# RAMPSXB.net
KiCad netlist of a schematic drawn in EAGLE
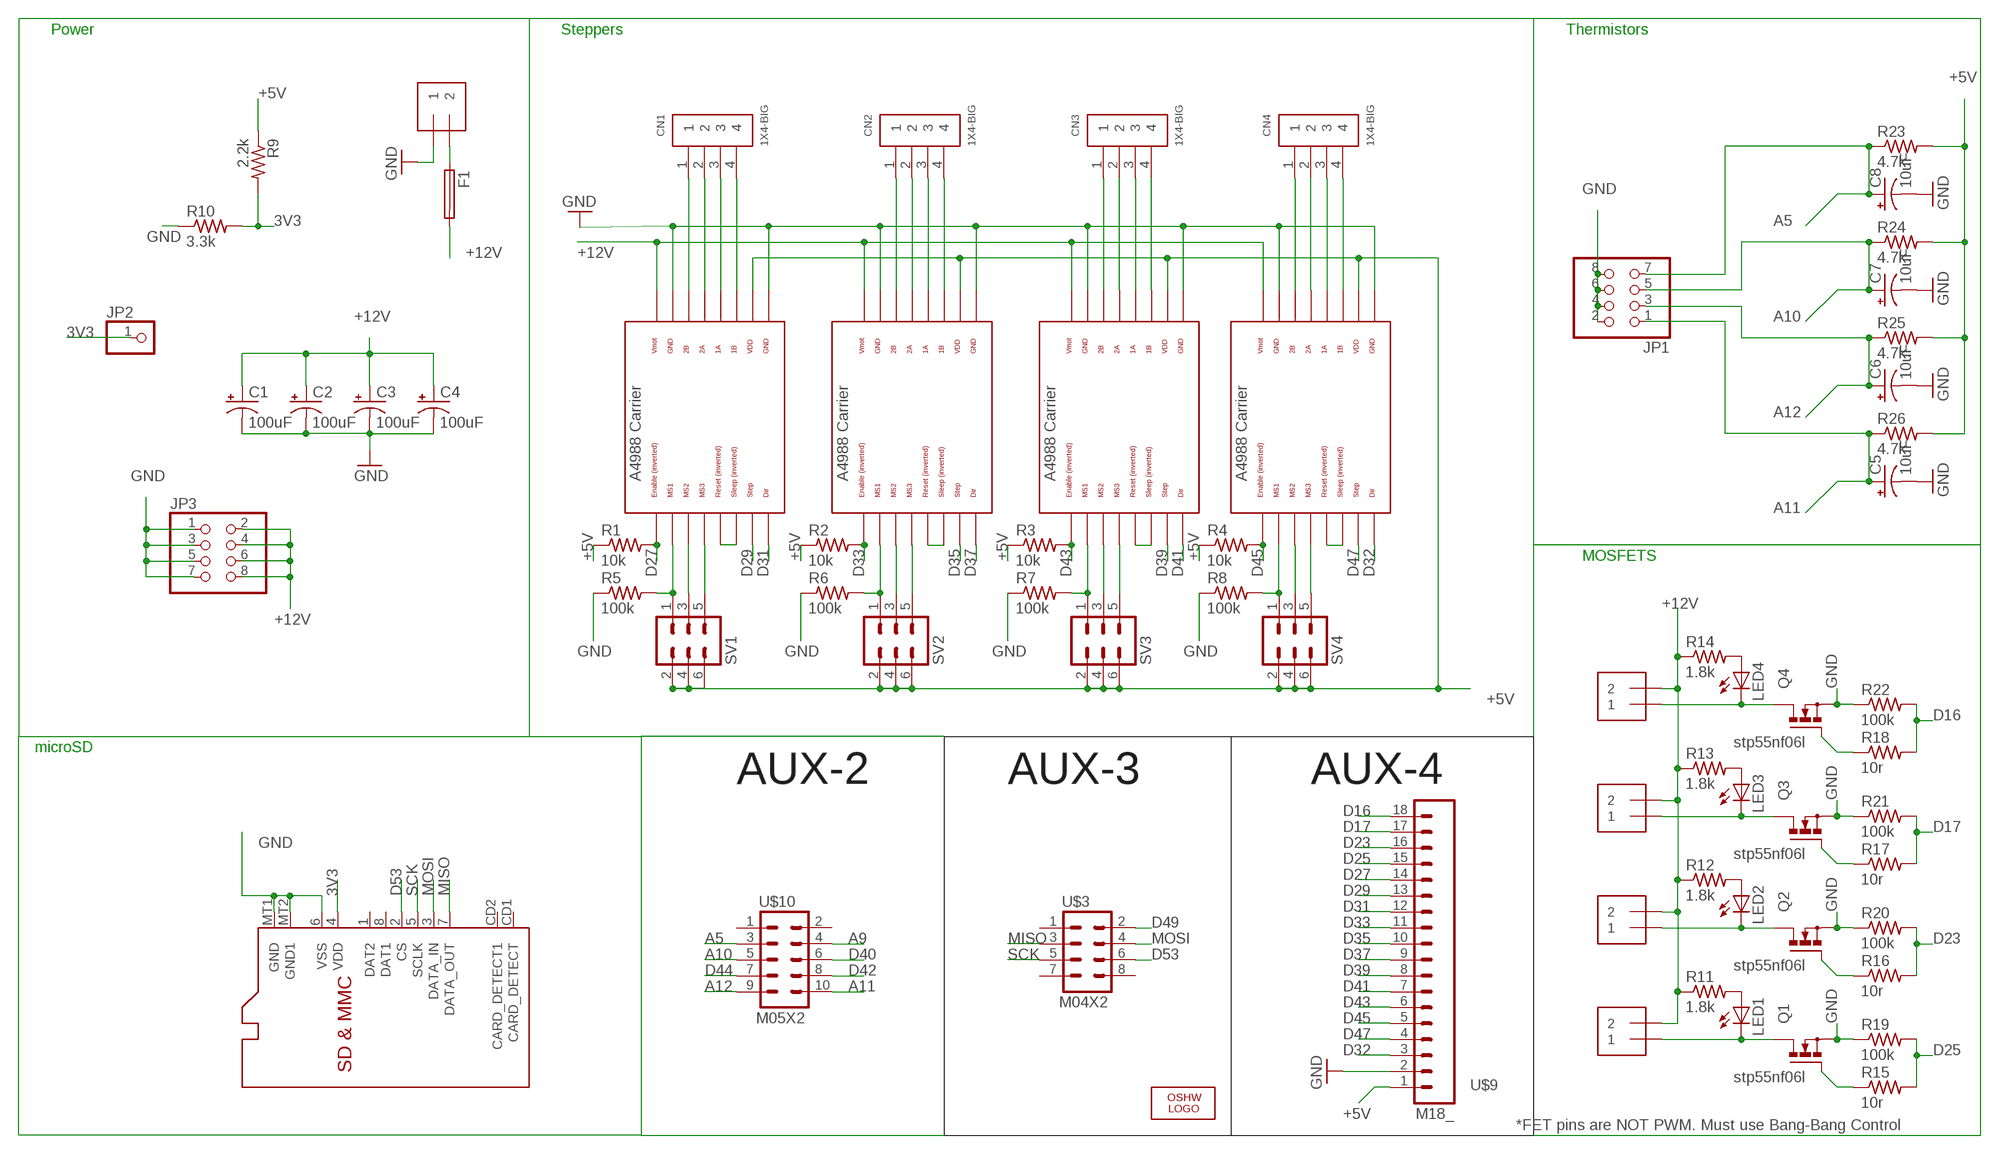
[diagram p0: schematic, sheet 1]

(export (version "E")
  (design (tool "Eeschema 10.0.6"))
  (components
    (comp (ref "C1")
      (value "100uF")
      (footprint "eagle-import:153CLV-0605")
      (libsource (lib "eagle-import") (part "CPOL-US153CLV-0605"))
    )
    (comp (ref "C2")
      (value "100uF")
      (footprint "eagle-import:153CLV-0605")
      (libsource (lib "eagle-import") (part "CPOL-US153CLV-0605"))
    )
    (comp (ref "C3")
      (value "100uF")
      (footprint "eagle-import:153CLV-0605")
      (libsource (lib "eagle-import") (part "CPOL-US153CLV-0605"))
    )
    (comp (ref "C4")
      (value "100uF")
      (footprint "eagle-import:153CLV-0605")
      (libsource (lib "eagle-import") (part "CPOL-US153CLV-0605"))
    )
    (comp (ref "C5")
      (value "10uF")
      (footprint "eagle-import:153CLV-0405")
      (libsource (lib "eagle-import") (part "CPOL-US153CLV-0405"))
    )
    (comp (ref "C6")
      (value "10uF")
      (footprint "eagle-import:153CLV-0405")
      (libsource (lib "eagle-import") (part "CPOL-US153CLV-0405"))
    )
    (comp (ref "C7")
      (value "10uF")
      (footprint "eagle-import:153CLV-0405")
      (libsource (lib "eagle-import") (part "CPOL-US153CLV-0405"))
    )
    (comp (ref "C8")
      (value "10uF")
      (footprint "eagle-import:153CLV-0405")
      (libsource (lib "eagle-import") (part "CPOL-US153CLV-0405"))
    )
    (comp (ref "CN1")
      (value "1X4-BIG")
      (footprint "eagle-import:1X04-BIG")
      (libsource (lib "eagle-import") (part "1X4-BIG"))
    )
    (comp (ref "CN2")
      (value "1X4-BIG")
      (footprint "eagle-import:1X04-BIG")
      (libsource (lib "eagle-import") (part "1X4-BIG"))
    )
    (comp (ref "CN3")
      (value "1X4-BIG")
      (footprint "eagle-import:1X04-BIG")
      (libsource (lib "eagle-import") (part "1X4-BIG"))
    )
    (comp (ref "CN4")
      (value "1X4-BIG")
      (footprint "eagle-import:1X04-BIG")
      (libsource (lib "eagle-import") (part "1X4-BIG"))
    )
    (comp (ref "F1")
      (value "SH22,5")
      (footprint "eagle-import:SH22,5")
      (fields (field (name "MF") "SCHURTER") (field (name "MPN") "0031.8201"))
      (libsource (lib "eagle-import") (part "SH22,5"))
    )
    (comp (ref "J1")
      (value "1X2-3.5MM")
      (footprint "eagle-import:1X2-3.5MM")
      (libsource (lib "eagle-import") (part "1X2-3.5MM"))
    )
    (comp (ref "J2")
      (value "1X2-3.5MM")
      (footprint "eagle-import:1X2-3.5MM")
      (libsource (lib "eagle-import") (part "1X2-3.5MM"))
    )
    (comp (ref "J3")
      (value "1X2-3.5MM")
      (footprint "eagle-import:1X2-3.5MM")
      (libsource (lib "eagle-import") (part "1X2-3.5MM"))
    )
    (comp (ref "J4")
      (value "1X2-3.5MM")
      (footprint "eagle-import:1X2-3.5MM")
      (libsource (lib "eagle-import") (part "1X2-3.5MM"))
    )
    (comp (ref "J5")
      (value "1X2-3.5MM")
      (footprint "eagle-import:1X2-3.5MM")
      (libsource (lib "eagle-import") (part "1X2-3.5MM"))
    )
    (comp (ref "JP1")
      (value "PINHD-2X4")
      (footprint "eagle-import:2X04")
      (libsource (lib "eagle-import") (part "PINHD-2X4"))
    )
    (comp (ref "JP2")
      (value "PINHD-1X1")
      (footprint "eagle-import:1X01")
      (libsource (lib "eagle-import") (part "PINHD-1X1"))
    )
    (comp (ref "JP3")
      (value "PINHD-2X4")
      (footprint "eagle-import:2X04")
      (libsource (lib "eagle-import") (part "PINHD-2X4"))
    )
    (comp (ref "LED1")
      (value "LEDCHIPLED_0805")
      (footprint "eagle-import:CHIPLED_0805")
      (libsource (lib "eagle-import") (part "LEDCHIPLED_0805"))
    )
    (comp (ref "LED2")
      (value "LEDCHIPLED_0805")
      (footprint "eagle-import:CHIPLED_0805")
      (libsource (lib "eagle-import") (part "LEDCHIPLED_0805"))
    )
    (comp (ref "LED3")
      (value "LEDCHIPLED_0805")
      (footprint "eagle-import:CHIPLED_0805")
      (libsource (lib "eagle-import") (part "LEDCHIPLED_0805"))
    )
    (comp (ref "LED4")
      (value "LEDCHIPLED_0805")
      (footprint "eagle-import:CHIPLED_0805")
      (libsource (lib "eagle-import") (part "LEDCHIPLED_0805"))
    )
    (comp (ref "LOGO1")
      (value "OSHW_LOGO_6MILX0100-NT")
      (footprint "eagle-import:OSHW_6X100_NOTEXT")
      (libsource (lib "eagle-import") (part "OSHW_LOGO_6MILX0100-NT"))
    )
    (comp (ref "Q1")
      (value "IRF512")
      (footprint "eagle-import:TO220BV")
      (libsource (lib "eagle-import") (part "IRF512"))
    )
    (comp (ref "Q2")
      (value "IRF512")
      (footprint "eagle-import:TO220BV")
      (libsource (lib "eagle-import") (part "IRF512"))
    )
    (comp (ref "Q3")
      (value "IRF512")
      (footprint "eagle-import:TO220BV")
      (libsource (lib "eagle-import") (part "IRF512"))
    )
    (comp (ref "Q4")
      (value "IRF512")
      (footprint "eagle-import:TO220BV")
      (libsource (lib "eagle-import") (part "IRF512"))
    )
    (comp (ref "R1")
      (value "10k")
      (footprint "eagle-import:M0805")
      (libsource (lib "eagle-import") (part "R-US_M0805"))
    )
    (comp (ref "R2")
      (value "10k")
      (footprint "eagle-import:M0805")
      (libsource (lib "eagle-import") (part "R-US_M0805"))
    )
    (comp (ref "R3")
      (value "10k")
      (footprint "eagle-import:M0805")
      (libsource (lib "eagle-import") (part "R-US_M0805"))
    )
    (comp (ref "R4")
      (value "10k")
      (footprint "eagle-import:M0805")
      (libsource (lib "eagle-import") (part "R-US_M0805"))
    )
    (comp (ref "R5")
      (value "100k")
      (footprint "eagle-import:M0805")
      (libsource (lib "eagle-import") (part "R-US_M0805"))
    )
    (comp (ref "R6")
      (value "100k")
      (footprint "eagle-import:M0805")
      (libsource (lib "eagle-import") (part "R-US_M0805"))
    )
    (comp (ref "R7")
      (value "100k")
      (footprint "eagle-import:M0805")
      (libsource (lib "eagle-import") (part "R-US_M0805"))
    )
    (comp (ref "R8")
      (value "100k")
      (footprint "eagle-import:M0805")
      (libsource (lib "eagle-import") (part "R-US_M0805"))
    )
    (comp (ref "R9")
      (value "2.2k")
      (footprint "eagle-import:M1206")
      (libsource (lib "eagle-import") (part "R-US_M1206"))
    )
    (comp (ref "R10")
      (value "3.3k")
      (footprint "eagle-import:M1206")
      (libsource (lib "eagle-import") (part "R-US_M1206"))
    )
    (comp (ref "R11")
      (value "1.8k")
      (footprint "eagle-import:M0805")
      (libsource (lib "eagle-import") (part "R-US_M0805"))
    )
    (comp (ref "R12")
      (value "1.8k")
      (footprint "eagle-import:M0805")
      (libsource (lib "eagle-import") (part "R-US_M0805"))
    )
    (comp (ref "R13")
      (value "1.8k")
      (footprint "eagle-import:M0805")
      (libsource (lib "eagle-import") (part "R-US_M0805"))
    )
    (comp (ref "R14")
      (value "1.8k")
      (footprint "eagle-import:M0805")
      (libsource (lib "eagle-import") (part "R-US_M0805"))
    )
    (comp (ref "R15")
      (value "10r")
      (footprint "eagle-import:M0805")
      (libsource (lib "eagle-import") (part "R-US_M0805"))
    )
    (comp (ref "R16")
      (value "10r")
      (footprint "eagle-import:M0805")
      (libsource (lib "eagle-import") (part "R-US_M0805"))
    )
    (comp (ref "R17")
      (value "10r")
      (footprint "eagle-import:M0805")
      (libsource (lib "eagle-import") (part "R-US_M0805"))
    )
    (comp (ref "R18")
      (value "10r")
      (footprint "eagle-import:M0805")
      (libsource (lib "eagle-import") (part "R-US_M0805"))
    )
    (comp (ref "R19")
      (value "100k")
      (footprint "eagle-import:M0805")
      (libsource (lib "eagle-import") (part "R-US_M0805"))
    )
    (comp (ref "R20")
      (value "100k")
      (footprint "eagle-import:M0805")
      (libsource (lib "eagle-import") (part "R-US_M0805"))
    )
    (comp (ref "R21")
      (value "100k")
      (footprint "eagle-import:M0805")
      (libsource (lib "eagle-import") (part "R-US_M0805"))
    )
    (comp (ref "R22")
      (value "100k")
      (footprint "eagle-import:M0805")
      (libsource (lib "eagle-import") (part "R-US_M0805"))
    )
    (comp (ref "R23")
      (value "4.7k")
      (footprint "eagle-import:R0805")
      (libsource (lib "eagle-import") (part "R-US_R0805"))
    )
    (comp (ref "R24")
      (value "4.7k")
      (footprint "eagle-import:R0805")
      (libsource (lib "eagle-import") (part "R-US_R0805"))
    )
    (comp (ref "R25")
      (value "4.7k")
      (footprint "eagle-import:R0805")
      (libsource (lib "eagle-import") (part "R-US_R0805"))
    )
    (comp (ref "R26")
      (value "4.7k")
      (footprint "eagle-import:R0805")
      (libsource (lib "eagle-import") (part "R-US_R0805"))
    )
    (comp (ref "SV1")
      (value "MA03-2")
      (footprint "eagle-import:MA03-2")
      (libsource (lib "eagle-import") (part "MA03-2"))
    )
    (comp (ref "SV2")
      (value "MA03-2")
      (footprint "eagle-import:MA03-2")
      (libsource (lib "eagle-import") (part "MA03-2"))
    )
    (comp (ref "SV3")
      (value "MA03-2")
      (footprint "eagle-import:MA03-2")
      (libsource (lib "eagle-import") (part "MA03-2"))
    )
    (comp (ref "SV4")
      (value "MA03-2")
      (footprint "eagle-import:MA03-2")
      (libsource (lib "eagle-import") (part "MA03-2"))
    )
    (comp (ref "U$1")
      (value "POLOLU_A4983CARRIER")
      (footprint "eagle-import:A4988BREAKOUT")
      (libsource (lib "eagle-import") (part "POLOLU_A4983CARRIER"))
    )
    (comp (ref "U$2")
      (value "POLOLU_A4983CARRIER")
      (footprint "eagle-import:A4988BREAKOUT")
      (libsource (lib "eagle-import") (part "POLOLU_A4983CARRIER"))
    )
    (comp (ref "U$3")
      (value "M04X2")
      (footprint "eagle-import:2X4")
      (libsource (lib "eagle-import") (part "M04X2"))
    )
    (comp (ref "U$4")
      (value "POLOLU_A4983CARRIER")
      (footprint "eagle-import:A4988BREAKOUT")
      (libsource (lib "eagle-import") (part "POLOLU_A4983CARRIER"))
    )
    (comp (ref "U$5")
      (value "POLOLU_A4983CARRIER")
      (footprint "eagle-import:A4988BREAKOUT")
      (libsource (lib "eagle-import") (part "POLOLU_A4983CARRIER"))
    )
    (comp (ref "U$6")
      (value "MICROSD")
      (footprint "eagle-import:MICROSD")
      (libsource (lib "eagle-import") (part "MICROSD"))
    )
    (comp (ref "U$9")
      (value "M18_")
      (footprint "eagle-import:1X18")
      (libsource (lib "eagle-import") (part "M18_"))
    )
    (comp (ref "U$10")
      (value "M05X2")
      (footprint "eagle-import:2X5")
      (libsource (lib "eagle-import") (part "M05X2"))
    )
  )
  (nets
    (net (code "1") (name "/+5V") (class "Default")
      (node (ref "R1") (pin "1") (pinfunction "1_1") (pintype "passive"))
      (node (ref "R2") (pin "1") (pinfunction "1_1") (pintype "passive"))
      (node (ref "R23") (pin "2") (pinfunction "2_2") (pintype "passive"))
      (node (ref "R24") (pin "2") (pinfunction "2_2") (pintype "passive"))
      (node (ref "R25") (pin "2") (pinfunction "2_2") (pintype "passive"))
      (node (ref "R26") (pin "2") (pinfunction "2_2") (pintype "passive"))
      (node (ref "R3") (pin "1") (pinfunction "1_1") (pintype "passive"))
      (node (ref "R4") (pin "1") (pinfunction "1_1") (pintype "passive"))
      (node (ref "R9") (pin "1") (pinfunction "1_1") (pintype "passive"))
      (node (ref "SV1") (pin "2") (pinfunction "2_2") (pintype "passive"))
      (node (ref "SV1") (pin "4") (pinfunction "4_4") (pintype "passive"))
      (node (ref "SV1") (pin "6") (pinfunction "6_6") (pintype "passive"))
      (node (ref "SV2") (pin "2") (pinfunction "2_2") (pintype "passive"))
      (node (ref "SV2") (pin "4") (pinfunction "4_4") (pintype "passive"))
      (node (ref "SV2") (pin "6") (pinfunction "6_6") (pintype "passive"))
      (node (ref "SV3") (pin "2") (pinfunction "2_2") (pintype "passive"))
      (node (ref "SV3") (pin "4") (pinfunction "4_4") (pintype "passive"))
      (node (ref "SV3") (pin "6") (pinfunction "6_6") (pintype "passive"))
      (node (ref "SV4") (pin "2") (pinfunction "2_2") (pintype "passive"))
      (node (ref "SV4") (pin "4") (pinfunction "4_4") (pintype "passive"))
      (node (ref "SV4") (pin "6") (pinfunction "6_6") (pintype "passive"))
      (node (ref "U$1") (pin "VDD") (pinfunction "VDD_VDD") (pintype "power_in"))
      (node (ref "U$2") (pin "VDD") (pinfunction "VDD_VDD") (pintype "power_in"))
      (node (ref "U$4") (pin "VDD") (pinfunction "VDD_VDD") (pintype "power_in"))
      (node (ref "U$5") (pin "VDD") (pinfunction "VDD_VDD") (pintype "power_in"))
      (node (ref "U$9") (pin "1") (pinfunction "1_1") (pintype "passive"))
    )
    (net (code "2") (name "/+12V") (class "Default")
      (node (ref "C1") (pin "+") (pinfunction "+_+") (pintype "passive"))
      (node (ref "C2") (pin "+") (pinfunction "+_+") (pintype "passive"))
      (node (ref "C3") (pin "+") (pinfunction "+_+") (pintype "passive"))
      (node (ref "C4") (pin "+") (pinfunction "+_+") (pintype "passive"))
      (node (ref "F1") (pin "2") (pinfunction "2_2") (pintype "passive"))
      (node (ref "J2") (pin "2") (pinfunction "2_2") (pintype "passive"))
      (node (ref "J3") (pin "2") (pinfunction "2_2") (pintype "passive"))
      (node (ref "J4") (pin "2") (pinfunction "2_2") (pintype "passive"))
      (node (ref "J5") (pin "2") (pinfunction "2_2") (pintype "passive"))
      (node (ref "JP3") (pin "2") (pinfunction "2_2") (pintype "passive"))
      (node (ref "JP3") (pin "4") (pinfunction "4_4") (pintype "passive"))
      (node (ref "JP3") (pin "6") (pinfunction "6_6") (pintype "passive"))
      (node (ref "JP3") (pin "8") (pinfunction "8_8") (pintype "passive"))
      (node (ref "R11") (pin "1") (pinfunction "1_1") (pintype "passive"))
      (node (ref "R12") (pin "1") (pinfunction "1_1") (pintype "passive"))
      (node (ref "R13") (pin "1") (pinfunction "1_1") (pintype "passive"))
      (node (ref "R14") (pin "1") (pinfunction "1_1") (pintype "passive"))
      (node (ref "U$1") (pin "VMOT") (pinfunction "VMOT_VMOT") (pintype "power_in"))
      (node (ref "U$2") (pin "VMOT") (pinfunction "VMOT_VMOT") (pintype "power_in"))
      (node (ref "U$4") (pin "VMOT") (pinfunction "VMOT_VMOT") (pintype "power_in"))
      (node (ref "U$5") (pin "VMOT") (pinfunction "VMOT_VMOT") (pintype "power_in"))
    )
    (net (code "3") (name "/3V3") (class "Default")
      (node (ref "JP2") (pin "1") (pinfunction "1_1") (pintype "passive"))
      (node (ref "R10") (pin "2") (pinfunction "2_2") (pintype "passive"))
      (node (ref "R9") (pin "2") (pinfunction "2_2") (pintype "passive"))
      (node (ref "U$6") (pin "4") (pinfunction "VDD_4") (pintype "power_in"))
    )
    (net (code "4") (name "/A5") (class "Default")
      (node (ref "C8") (pin "+") (pinfunction "+_+") (pintype "passive"))
      (node (ref "JP1") (pin "7") (pinfunction "7_7") (pintype "passive"))
      (node (ref "R23") (pin "1") (pinfunction "1_1") (pintype "passive"))
      (node (ref "U$10") (pin "3") (pinfunction "3_3") (pintype "passive"))
    )
    (net (code "5") (name "/A9") (class "Default")
      (node (ref "U$10") (pin "4") (pinfunction "4_4") (pintype "passive"))
    )
    (net (code "6") (name "/A10") (class "Default")
      (node (ref "C7") (pin "+") (pinfunction "+_+") (pintype "passive"))
      (node (ref "JP1") (pin "5") (pinfunction "5_5") (pintype "passive"))
      (node (ref "R24") (pin "1") (pinfunction "1_1") (pintype "passive"))
      (node (ref "U$10") (pin "5") (pinfunction "5_5") (pintype "passive"))
    )
    (net (code "7") (name "/A11") (class "Default")
      (node (ref "C5") (pin "+") (pinfunction "+_+") (pintype "passive"))
      (node (ref "JP1") (pin "1") (pinfunction "1_1") (pintype "passive"))
      (node (ref "R26") (pin "1") (pinfunction "1_1") (pintype "passive"))
      (node (ref "U$10") (pin "10") (pinfunction "10_10") (pintype "passive"))
    )
    (net (code "8") (name "/A12") (class "Default")
      (node (ref "C6") (pin "+") (pinfunction "+_+") (pintype "passive"))
      (node (ref "JP1") (pin "3") (pinfunction "3_3") (pintype "passive"))
      (node (ref "R25") (pin "1") (pinfunction "1_1") (pintype "passive"))
      (node (ref "U$10") (pin "9") (pinfunction "9_9") (pintype "passive"))
    )
    (net (code "9") (name "/D16") (class "Default")
      (node (ref "R18") (pin "2") (pinfunction "2_2") (pintype "passive"))
      (node (ref "R22") (pin "2") (pinfunction "2_2") (pintype "passive"))
      (node (ref "U$9") (pin "18") (pinfunction "18_18") (pintype "passive"))
    )
    (net (code "10") (name "/D17") (class "Default")
      (node (ref "R17") (pin "2") (pinfunction "2_2") (pintype "passive"))
      (node (ref "R21") (pin "2") (pinfunction "2_2") (pintype "passive"))
      (node (ref "U$9") (pin "17") (pinfunction "17_17") (pintype "passive"))
    )
    (net (code "11") (name "/D23") (class "Default")
      (node (ref "R16") (pin "2") (pinfunction "2_2") (pintype "passive"))
      (node (ref "R20") (pin "2") (pinfunction "2_2") (pintype "passive"))
      (node (ref "U$9") (pin "16") (pinfunction "16_16") (pintype "passive"))
    )
    (net (code "12") (name "/D25") (class "Default")
      (node (ref "R15") (pin "2") (pinfunction "2_2") (pintype "passive"))
      (node (ref "R19") (pin "2") (pinfunction "2_2") (pintype "passive"))
      (node (ref "U$9") (pin "15") (pinfunction "15_15") (pintype "passive"))
    )
    (net (code "13") (name "/D27") (class "Default")
      (node (ref "R1") (pin "2") (pinfunction "2_2") (pintype "passive"))
      (node (ref "U$1") (pin "EN") (pinfunction "EN_EN") (pintype "input"))
      (node (ref "U$9") (pin "14") (pinfunction "14_14") (pintype "passive"))
    )
    (net (code "14") (name "/D29") (class "Default")
      (node (ref "U$1") (pin "STEP") (pinfunction "STEP_STEP") (pintype "input"))
      (node (ref "U$9") (pin "13") (pinfunction "13_13") (pintype "passive"))
    )
    (net (code "15") (name "/D31") (class "Default")
      (node (ref "U$1") (pin "DIR") (pinfunction "DIR_DIR") (pintype "input"))
      (node (ref "U$9") (pin "12") (pinfunction "12_12") (pintype "passive"))
    )
    (net (code "16") (name "/D32") (class "Default")
      (node (ref "U$5") (pin "DIR") (pinfunction "DIR_DIR") (pintype "input"))
      (node (ref "U$9") (pin "3") (pinfunction "3_3") (pintype "passive"))
    )
    (net (code "17") (name "/D33") (class "Default")
      (node (ref "R2") (pin "2") (pinfunction "2_2") (pintype "passive"))
      (node (ref "U$2") (pin "EN") (pinfunction "EN_EN") (pintype "input"))
      (node (ref "U$9") (pin "11") (pinfunction "11_11") (pintype "passive"))
    )
    (net (code "18") (name "/D35") (class "Default")
      (node (ref "U$2") (pin "STEP") (pinfunction "STEP_STEP") (pintype "input"))
      (node (ref "U$9") (pin "10") (pinfunction "10_10") (pintype "passive"))
    )
    (net (code "19") (name "/D37") (class "Default")
      (node (ref "U$2") (pin "DIR") (pinfunction "DIR_DIR") (pintype "input"))
      (node (ref "U$9") (pin "9") (pinfunction "9_9") (pintype "passive"))
    )
    (net (code "20") (name "/D39") (class "Default")
      (node (ref "U$4") (pin "STEP") (pinfunction "STEP_STEP") (pintype "input"))
      (node (ref "U$9") (pin "8") (pinfunction "8_8") (pintype "passive"))
    )
    (net (code "21") (name "/D40") (class "Default")
      (node (ref "U$10") (pin "6") (pinfunction "6_6") (pintype "passive"))
    )
    (net (code "22") (name "/D41") (class "Default")
      (node (ref "U$4") (pin "DIR") (pinfunction "DIR_DIR") (pintype "input"))
      (node (ref "U$9") (pin "7") (pinfunction "7_7") (pintype "passive"))
    )
    (net (code "23") (name "/D42") (class "Default")
      (node (ref "U$10") (pin "8") (pinfunction "8_8") (pintype "passive"))
    )
    (net (code "24") (name "/D43") (class "Default")
      (node (ref "R3") (pin "2") (pinfunction "2_2") (pintype "passive"))
      (node (ref "U$4") (pin "EN") (pinfunction "EN_EN") (pintype "input"))
      (node (ref "U$9") (pin "6") (pinfunction "6_6") (pintype "passive"))
    )
    (net (code "25") (name "/D44") (class "Default")
      (node (ref "U$10") (pin "7") (pinfunction "7_7") (pintype "passive"))
    )
    (net (code "26") (name "/D45") (class "Default")
      (node (ref "R4") (pin "2") (pinfunction "2_2") (pintype "passive"))
      (node (ref "U$5") (pin "EN") (pinfunction "EN_EN") (pintype "input"))
      (node (ref "U$9") (pin "5") (pinfunction "5_5") (pintype "passive"))
    )
    (net (code "27") (name "/D47") (class "Default")
      (node (ref "U$5") (pin "STEP") (pinfunction "STEP_STEP") (pintype "input"))
      (node (ref "U$9") (pin "4") (pinfunction "4_4") (pintype "passive"))
    )
    (net (code "28") (name "/D49") (class "Default")
      (node (ref "U$3") (pin "2") (pinfunction "2_2") (pintype "passive"))
    )
    (net (code "29") (name "/D53") (class "Default")
      (node (ref "U$3") (pin "6") (pinfunction "6_6") (pintype "passive"))
      (node (ref "U$6") (pin "2") (pinfunction "CS_2") (pintype "input"))
    )
    (net (code "30") (name "/MISO") (class "Default")
      (node (ref "U$3") (pin "3") (pinfunction "3_3") (pintype "passive"))
      (node (ref "U$6") (pin "7") (pinfunction "DATA_OUT_7") (pintype "output"))
    )
    (net (code "31") (name "/MOSI") (class "Default")
      (node (ref "U$3") (pin "4") (pinfunction "4_4") (pintype "passive"))
      (node (ref "U$6") (pin "3") (pinfunction "DATA_IN_3") (pintype "input"))
    )
    (net (code "32") (name "/SCK") (class "Default")
      (node (ref "U$3") (pin "5") (pinfunction "5_5") (pintype "passive"))
      (node (ref "U$6") (pin "5") (pinfunction "SCLK_5") (pintype "input"))
    )
    (net (code "33") (name "GND") (class "Default")
      (node (ref "C1") (pin "-") (pinfunction "-_-") (pintype "passive"))
      (node (ref "C2") (pin "-") (pinfunction "-_-") (pintype "passive"))
      (node (ref "C3") (pin "-") (pinfunction "-_-") (pintype "passive"))
      (node (ref "C4") (pin "-") (pinfunction "-_-") (pintype "passive"))
      (node (ref "C5") (pin "-") (pinfunction "-_-") (pintype "passive"))
      (node (ref "C6") (pin "-") (pinfunction "-_-") (pintype "passive"))
      (node (ref "C7") (pin "-") (pinfunction "-_-") (pintype "passive"))
      (node (ref "C8") (pin "-") (pinfunction "-_-") (pintype "passive"))
      (node (ref "J1") (pin "1") (pinfunction "1_1") (pintype "passive"))
      (node (ref "JP1") (pin "2") (pinfunction "2_2") (pintype "passive"))
      (node (ref "JP1") (pin "4") (pinfunction "4_4") (pintype "passive"))
      (node (ref "JP1") (pin "6") (pinfunction "6_6") (pintype "passive"))
      (node (ref "JP1") (pin "8") (pinfunction "8_8") (pintype "passive"))
      (node (ref "JP3") (pin "1") (pinfunction "1_1") (pintype "passive"))
      (node (ref "JP3") (pin "3") (pinfunction "3_3") (pintype "passive"))
      (node (ref "JP3") (pin "5") (pinfunction "5_5") (pintype "passive"))
      (node (ref "JP3") (pin "7") (pinfunction "7_7") (pintype "passive"))
      (node (ref "Q1") (pin "S") (pinfunction "S_S") (pintype "passive"))
      (node (ref "Q2") (pin "S") (pinfunction "S_S") (pintype "passive"))
      (node (ref "Q3") (pin "S") (pinfunction "S_S") (pintype "passive"))
      (node (ref "Q4") (pin "S") (pinfunction "S_S") (pintype "passive"))
      (node (ref "R10") (pin "1") (pinfunction "1_1") (pintype "passive"))
      (node (ref "R19") (pin "1") (pinfunction "1_1") (pintype "passive"))
      (node (ref "R20") (pin "1") (pinfunction "1_1") (pintype "passive"))
      (node (ref "R21") (pin "1") (pinfunction "1_1") (pintype "passive"))
      (node (ref "R22") (pin "1") (pinfunction "1_1") (pintype "passive"))
      (node (ref "R5") (pin "1") (pinfunction "1_1") (pintype "passive"))
      (node (ref "R6") (pin "1") (pinfunction "1_1") (pintype "passive"))
      (node (ref "R7") (pin "1") (pinfunction "1_1") (pintype "passive"))
      (node (ref "R8") (pin "1") (pinfunction "1_1") (pintype "passive"))
      (node (ref "U$1") (pin "GND") (pinfunction "GND_GND") (pintype "power_in"))
      (node (ref "U$1") (pin "GND@0") (pinfunction "GND_GND@0") (pintype "power_in"))
      (node (ref "U$2") (pin "GND") (pinfunction "GND_GND") (pintype "power_in"))
      (node (ref "U$2") (pin "GND@0") (pinfunction "GND_GND@0") (pintype "power_in"))
      (node (ref "U$4") (pin "GND") (pinfunction "GND_GND") (pintype "power_in"))
      (node (ref "U$4") (pin "GND@0") (pinfunction "GND_GND@0") (pintype "power_in"))
      (node (ref "U$5") (pin "GND") (pinfunction "GND_GND") (pintype "power_in"))
      (node (ref "U$5") (pin "GND@0") (pinfunction "GND_GND@0") (pintype "power_in"))
      (node (ref "U$6") (pin "6") (pinfunction "VSS_6") (pintype "power_in"))
      (node (ref "U$6") (pin "MT1") (pinfunction "GND_MT1") (pintype "power_in"))
      (node (ref "U$6") (pin "MT2") (pinfunction "GND1_MT2") (pintype "power_in"))
      (node (ref "U$9") (pin "2") (pinfunction "2_2") (pintype "passive"))
    )
    (net (code "34") (name "Net-(CN1-Pad1)") (class "Default")
      (node (ref "CN1") (pin "1") (pinfunction "1_1") (pintype "bidirectional"))
      (node (ref "U$1") (pin "2B") (pinfunction "2B_2B") (pintype "output"))
    )
    (net (code "35") (name "Net-(CN1-Pad2)") (class "Default")
      (node (ref "CN1") (pin "2") (pinfunction "2_2") (pintype "bidirectional"))
      (node (ref "U$1") (pin "2A") (pinfunction "2A_2A") (pintype "output"))
    )
    (net (code "36") (name "Net-(CN1-Pad3)") (class "Default")
      (node (ref "CN1") (pin "3") (pinfunction "3_3") (pintype "bidirectional"))
      (node (ref "U$1") (pin "1A") (pinfunction "1A_1A") (pintype "output"))
    )
    (net (code "37") (name "Net-(CN1-Pad4)") (class "Default")
      (node (ref "CN1") (pin "4") (pinfunction "4_4") (pintype "bidirectional"))
      (node (ref "U$1") (pin "1B") (pinfunction "1B_1B") (pintype "output"))
    )
    (net (code "38") (name "Net-(CN2-Pad1)") (class "Default")
      (node (ref "CN2") (pin "1") (pinfunction "1_1") (pintype "bidirectional"))
      (node (ref "U$2") (pin "2B") (pinfunction "2B_2B") (pintype "output"))
    )
    (net (code "39") (name "Net-(CN2-Pad2)") (class "Default")
      (node (ref "CN2") (pin "2") (pinfunction "2_2") (pintype "bidirectional"))
      (node (ref "U$2") (pin "2A") (pinfunction "2A_2A") (pintype "output"))
    )
    (net (code "40") (name "Net-(CN2-Pad3)") (class "Default")
      (node (ref "CN2") (pin "3") (pinfunction "3_3") (pintype "bidirectional"))
      (node (ref "U$2") (pin "1A") (pinfunction "1A_1A") (pintype "output"))
    )
    (net (code "41") (name "Net-(CN2-Pad4)") (class "Default")
      (node (ref "CN2") (pin "4") (pinfunction "4_4") (pintype "bidirectional"))
      (node (ref "U$2") (pin "1B") (pinfunction "1B_1B") (pintype "output"))
    )
    (net (code "42") (name "Net-(CN3-Pad1)") (class "Default")
      (node (ref "CN3") (pin "1") (pinfunction "1_1") (pintype "bidirectional"))
      (node (ref "U$4") (pin "2B") (pinfunction "2B_2B") (pintype "output"))
    )
    (net (code "43") (name "Net-(CN3-Pad2)") (class "Default")
      (node (ref "CN3") (pin "2") (pinfunction "2_2") (pintype "bidirectional"))
      (node (ref "U$4") (pin "2A") (pinfunction "2A_2A") (pintype "output"))
    )
    (net (code "44") (name "Net-(CN3-Pad3)") (class "Default")
      (node (ref "CN3") (pin "3") (pinfunction "3_3") (pintype "bidirectional"))
      (node (ref "U$4") (pin "1A") (pinfunction "1A_1A") (pintype "output"))
    )
    (net (code "45") (name "Net-(CN3-Pad4)") (class "Default")
      (node (ref "CN3") (pin "4") (pinfunction "4_4") (pintype "bidirectional"))
      (node (ref "U$4") (pin "1B") (pinfunction "1B_1B") (pintype "output"))
    )
    (net (code "46") (name "Net-(CN4-Pad1)") (class "Default")
      (node (ref "CN4") (pin "1") (pinfunction "1_1") (pintype "bidirectional"))
      (node (ref "U$5") (pin "2B") (pinfunction "2B_2B") (pintype "output"))
    )
    (net (code "47") (name "Net-(CN4-Pad2)") (class "Default")
      (node (ref "CN4") (pin "2") (pinfunction "2_2") (pintype "bidirectional"))
      (node (ref "U$5") (pin "2A") (pinfunction "2A_2A") (pintype "output"))
    )
    (net (code "48") (name "Net-(CN4-Pad3)") (class "Default")
      (node (ref "CN4") (pin "3") (pinfunction "3_3") (pintype "bidirectional"))
      (node (ref "U$5") (pin "1A") (pinfunction "1A_1A") (pintype "output"))
    )
    (net (code "49") (name "Net-(CN4-Pad4)") (class "Default")
      (node (ref "CN4") (pin "4") (pinfunction "4_4") (pintype "bidirectional"))
      (node (ref "U$5") (pin "1B") (pinfunction "1B_1B") (pintype "output"))
    )
    (net (code "50") (name "Net-(F1-Pad1)") (class "Default")
      (node (ref "F1") (pin "1") (pinfunction "1_1") (pintype "passive"))
      (node (ref "J1") (pin "2") (pinfunction "2_2") (pintype "passive"))
    )
    (net (code "51") (name "Net-(J2-Pad1)") (class "Default")
      (node (ref "J2") (pin "1") (pinfunction "1_1") (pintype "passive"))
      (node (ref "LED1") (pin "C") (pinfunction "C_C") (pintype "passive"))
      (node (ref "Q1") (pin "D") (pinfunction "D_D") (pintype "passive"))
    )
    (net (code "52") (name "Net-(J3-Pad1)") (class "Default")
      (node (ref "J3") (pin "1") (pinfunction "1_1") (pintype "passive"))
      (node (ref "LED2") (pin "C") (pinfunction "C_C") (pintype "passive"))
      (node (ref "Q2") (pin "D") (pinfunction "D_D") (pintype "passive"))
    )
    (net (code "53") (name "Net-(J4-Pad1)") (class "Default")
      (node (ref "J4") (pin "1") (pinfunction "1_1") (pintype "passive"))
      (node (ref "LED3") (pin "C") (pinfunction "C_C") (pintype "passive"))
      (node (ref "Q3") (pin "D") (pinfunction "D_D") (pintype "passive"))
    )
    (net (code "54") (name "Net-(J5-Pad1)") (class "Default")
      (node (ref "J5") (pin "1") (pinfunction "1_1") (pintype "passive"))
      (node (ref "LED4") (pin "C") (pinfunction "C_C") (pintype "passive"))
      (node (ref "Q4") (pin "D") (pinfunction "D_D") (pintype "passive"))
    )
    (net (code "55") (name "Net-(LED1-PadA)") (class "Default")
      (node (ref "LED1") (pin "A") (pinfunction "A_A") (pintype "passive"))
      (node (ref "R11") (pin "2") (pinfunction "2_2") (pintype "passive"))
    )
    (net (code "56") (name "Net-(LED2-PadA)") (class "Default")
      (node (ref "LED2") (pin "A") (pinfunction "A_A") (pintype "passive"))
      (node (ref "R12") (pin "2") (pinfunction "2_2") (pintype "passive"))
    )
    (net (code "57") (name "Net-(LED3-PadA)") (class "Default")
      (node (ref "LED3") (pin "A") (pinfunction "A_A") (pintype "passive"))
      (node (ref "R13") (pin "2") (pinfunction "2_2") (pintype "passive"))
    )
    (net (code "58") (name "Net-(LED4-PadA)") (class "Default")
      (node (ref "LED4") (pin "A") (pinfunction "A_A") (pintype "passive"))
      (node (ref "R14") (pin "2") (pinfunction "2_2") (pintype "passive"))
    )
    (net (code "59") (name "Net-(Q1-PadG)") (class "Default")
      (node (ref "Q1") (pin "G") (pinfunction "G_G") (pintype "passive"))
      (node (ref "R15") (pin "1") (pinfunction "1_1") (pintype "passive"))
    )
    (net (code "60") (name "Net-(Q2-PadG)") (class "Default")
      (node (ref "Q2") (pin "G") (pinfunction "G_G") (pintype "passive"))
      (node (ref "R16") (pin "1") (pinfunction "1_1") (pintype "passive"))
    )
    (net (code "61") (name "Net-(Q3-PadG)") (class "Default")
      (node (ref "Q3") (pin "G") (pinfunction "G_G") (pintype "passive"))
      (node (ref "R17") (pin "1") (pinfunction "1_1") (pintype "passive"))
    )
    (net (code "62") (name "Net-(Q4-PadG)") (class "Default")
      (node (ref "Q4") (pin "G") (pinfunction "G_G") (pintype "passive"))
      (node (ref "R18") (pin "1") (pinfunction "1_1") (pintype "passive"))
    )
    (net (code "63") (name "Net-(R5-Pad2)") (class "Default")
      (node (ref "R5") (pin "2") (pinfunction "2_2") (pintype "passive"))
      (node (ref "SV1") (pin "1") (pinfunction "1_1") (pintype "passive"))
      (node (ref "U$1") (pin "MS1") (pinfunction "MS1_MS1") (pintype "input"))
    )
    (net (code "64") (name "Net-(R6-Pad2)") (class "Default")
      (node (ref "R6") (pin "2") (pinfunction "2_2") (pintype "passive"))
      (node (ref "SV2") (pin "1") (pinfunction "1_1") (pintype "passive"))
      (node (ref "U$2") (pin "MS1") (pinfunction "MS1_MS1") (pintype "input"))
    )
    (net (code "65") (name "Net-(R7-Pad2)") (class "Default")
      (node (ref "R7") (pin "2") (pinfunction "2_2") (pintype "passive"))
      (node (ref "SV3") (pin "1") (pinfunction "1_1") (pintype "passive"))
      (node (ref "U$4") (pin "MS1") (pinfunction "MS1_MS1") (pintype "input"))
    )
    (net (code "66") (name "Net-(R8-Pad2)") (class "Default")
      (node (ref "R8") (pin "2") (pinfunction "2_2") (pintype "passive"))
      (node (ref "SV4") (pin "1") (pinfunction "1_1") (pintype "passive"))
      (node (ref "U$5") (pin "MS1") (pinfunction "MS1_MS1") (pintype "input"))
    )
    (net (code "67") (name "Net-(SV1-Pad3)") (class "Default")
      (node (ref "SV1") (pin "3") (pinfunction "3_3") (pintype "passive"))
      (node (ref "U$1") (pin "MS2") (pinfunction "MS2_MS2") (pintype "input"))
    )
    (net (code "68") (name "Net-(SV1-Pad5)") (class "Default")
      (node (ref "SV1") (pin "5") (pinfunction "5_5") (pintype "passive"))
      (node (ref "U$1") (pin "MS3") (pinfunction "MS3_MS3") (pintype "input"))
    )
    (net (code "69") (name "Net-(SV2-Pad3)") (class "Default")
      (node (ref "SV2") (pin "3") (pinfunction "3_3") (pintype "passive"))
      (node (ref "U$2") (pin "MS2") (pinfunction "MS2_MS2") (pintype "input"))
    )
    (net (code "70") (name "Net-(SV2-Pad5)") (class "Default")
      (node (ref "SV2") (pin "5") (pinfunction "5_5") (pintype "passive"))
      (node (ref "U$2") (pin "MS3") (pinfunction "MS3_MS3") (pintype "input"))
    )
    (net (code "71") (name "Net-(SV3-Pad3)") (class "Default")
      (node (ref "SV3") (pin "3") (pinfunction "3_3") (pintype "passive"))
      (node (ref "U$4") (pin "MS2") (pinfunction "MS2_MS2") (pintype "input"))
    )
    (net (code "72") (name "Net-(SV3-Pad5)") (class "Default")
      (node (ref "SV3") (pin "5") (pinfunction "5_5") (pintype "passive"))
      (node (ref "U$4") (pin "MS3") (pinfunction "MS3_MS3") (pintype "input"))
    )
    (net (code "73") (name "Net-(SV4-Pad3)") (class "Default")
      (node (ref "SV4") (pin "3") (pinfunction "3_3") (pintype "passive"))
      (node (ref "U$5") (pin "MS2") (pinfunction "MS2_MS2") (pintype "input"))
    )
    (net (code "74") (name "Net-(SV4-Pad5)") (class "Default")
      (node (ref "SV4") (pin "5") (pinfunction "5_5") (pintype "passive"))
      (node (ref "U$5") (pin "MS3") (pinfunction "MS3_MS3") (pintype "input"))
    )
    (net (code "75") (name "Net-(U$1-SLEEP)") (class "Default")
      (node (ref "U$1") (pin "RST") (pinfunction "RST_RST") (pintype "input"))
      (node (ref "U$1") (pin "SLP") (pinfunction "SLEEP_SLP") (pintype "input"))
    )
    (net (code "76") (name "Net-(U$2-SLEEP)") (class "Default")
      (node (ref "U$2") (pin "RST") (pinfunction "RST_RST") (pintype "input"))
      (node (ref "U$2") (pin "SLP") (pinfunction "SLEEP_SLP") (pintype "input"))
    )
    (net (code "77") (name "Net-(U$4-SLEEP)") (class "Default")
      (node (ref "U$4") (pin "RST") (pinfunction "RST_RST") (pintype "input"))
      (node (ref "U$4") (pin "SLP") (pinfunction "SLEEP_SLP") (pintype "input"))
    )
    (net (code "78") (name "Net-(U$5-SLEEP)") (class "Default")
      (node (ref "U$5") (pin "RST") (pinfunction "RST_RST") (pintype "input"))
      (node (ref "U$5") (pin "SLP") (pinfunction "SLEEP_SLP") (pintype "input"))
    )
    (net (code "79") (name "unconnected-(U$3-Pad1)") (class "Default")
      (node (ref "U$3") (pin "1") (pinfunction "1_1") (pintype "passive"))
    )
    (net (code "80") (name "unconnected-(U$3-Pad7)") (class "Default")
      (node (ref "U$3") (pin "7") (pinfunction "7_7") (pintype "passive"))
    )
    (net (code "81") (name "unconnected-(U$3-Pad8)") (class "Default")
      (node (ref "U$3") (pin "8") (pinfunction "8_8") (pintype "passive"))
    )
    (net (code "82") (name "unconnected-(U$6-CARD_DETECT-PadCD1)") (class "Default")
      (node (ref "U$6") (pin "CD1") (pinfunction "CARD_DETECT_CD1") (pintype "passive"))
    )
    (net (code "83") (name "unconnected-(U$6-CARD_DETECT1-PadCD2)") (class "Default")
      (node (ref "U$6") (pin "CD2") (pinfunction "CARD_DETECT1_CD2") (pintype "passive"))
    )
    (net (code "84") (name "unconnected-(U$6-DAT1-Pad8)") (class "Default")
      (node (ref "U$6") (pin "8") (pinfunction "DAT1_8") (pintype "bidirectional"))
    )
    (net (code "85") (name "unconnected-(U$6-DAT2-Pad1)") (class "Default")
      (node (ref "U$6") (pin "1") (pinfunction "DAT2_1") (pintype "bidirectional"))
    )
    (net (code "86") (name "unconnected-(U$10-Pad1)") (class "Default")
      (node (ref "U$10") (pin "1") (pinfunction "1_1") (pintype "passive"))
    )
    (net (code "87") (name "unconnected-(U$10-Pad2)") (class "Default")
      (node (ref "U$10") (pin "2") (pinfunction "2_2") (pintype "passive"))
    )
  )
)
